# SCH_Satlla_4_Power_Board_2023-01-29.net
KiCad netlist of a schematic drawn in EasyEDA
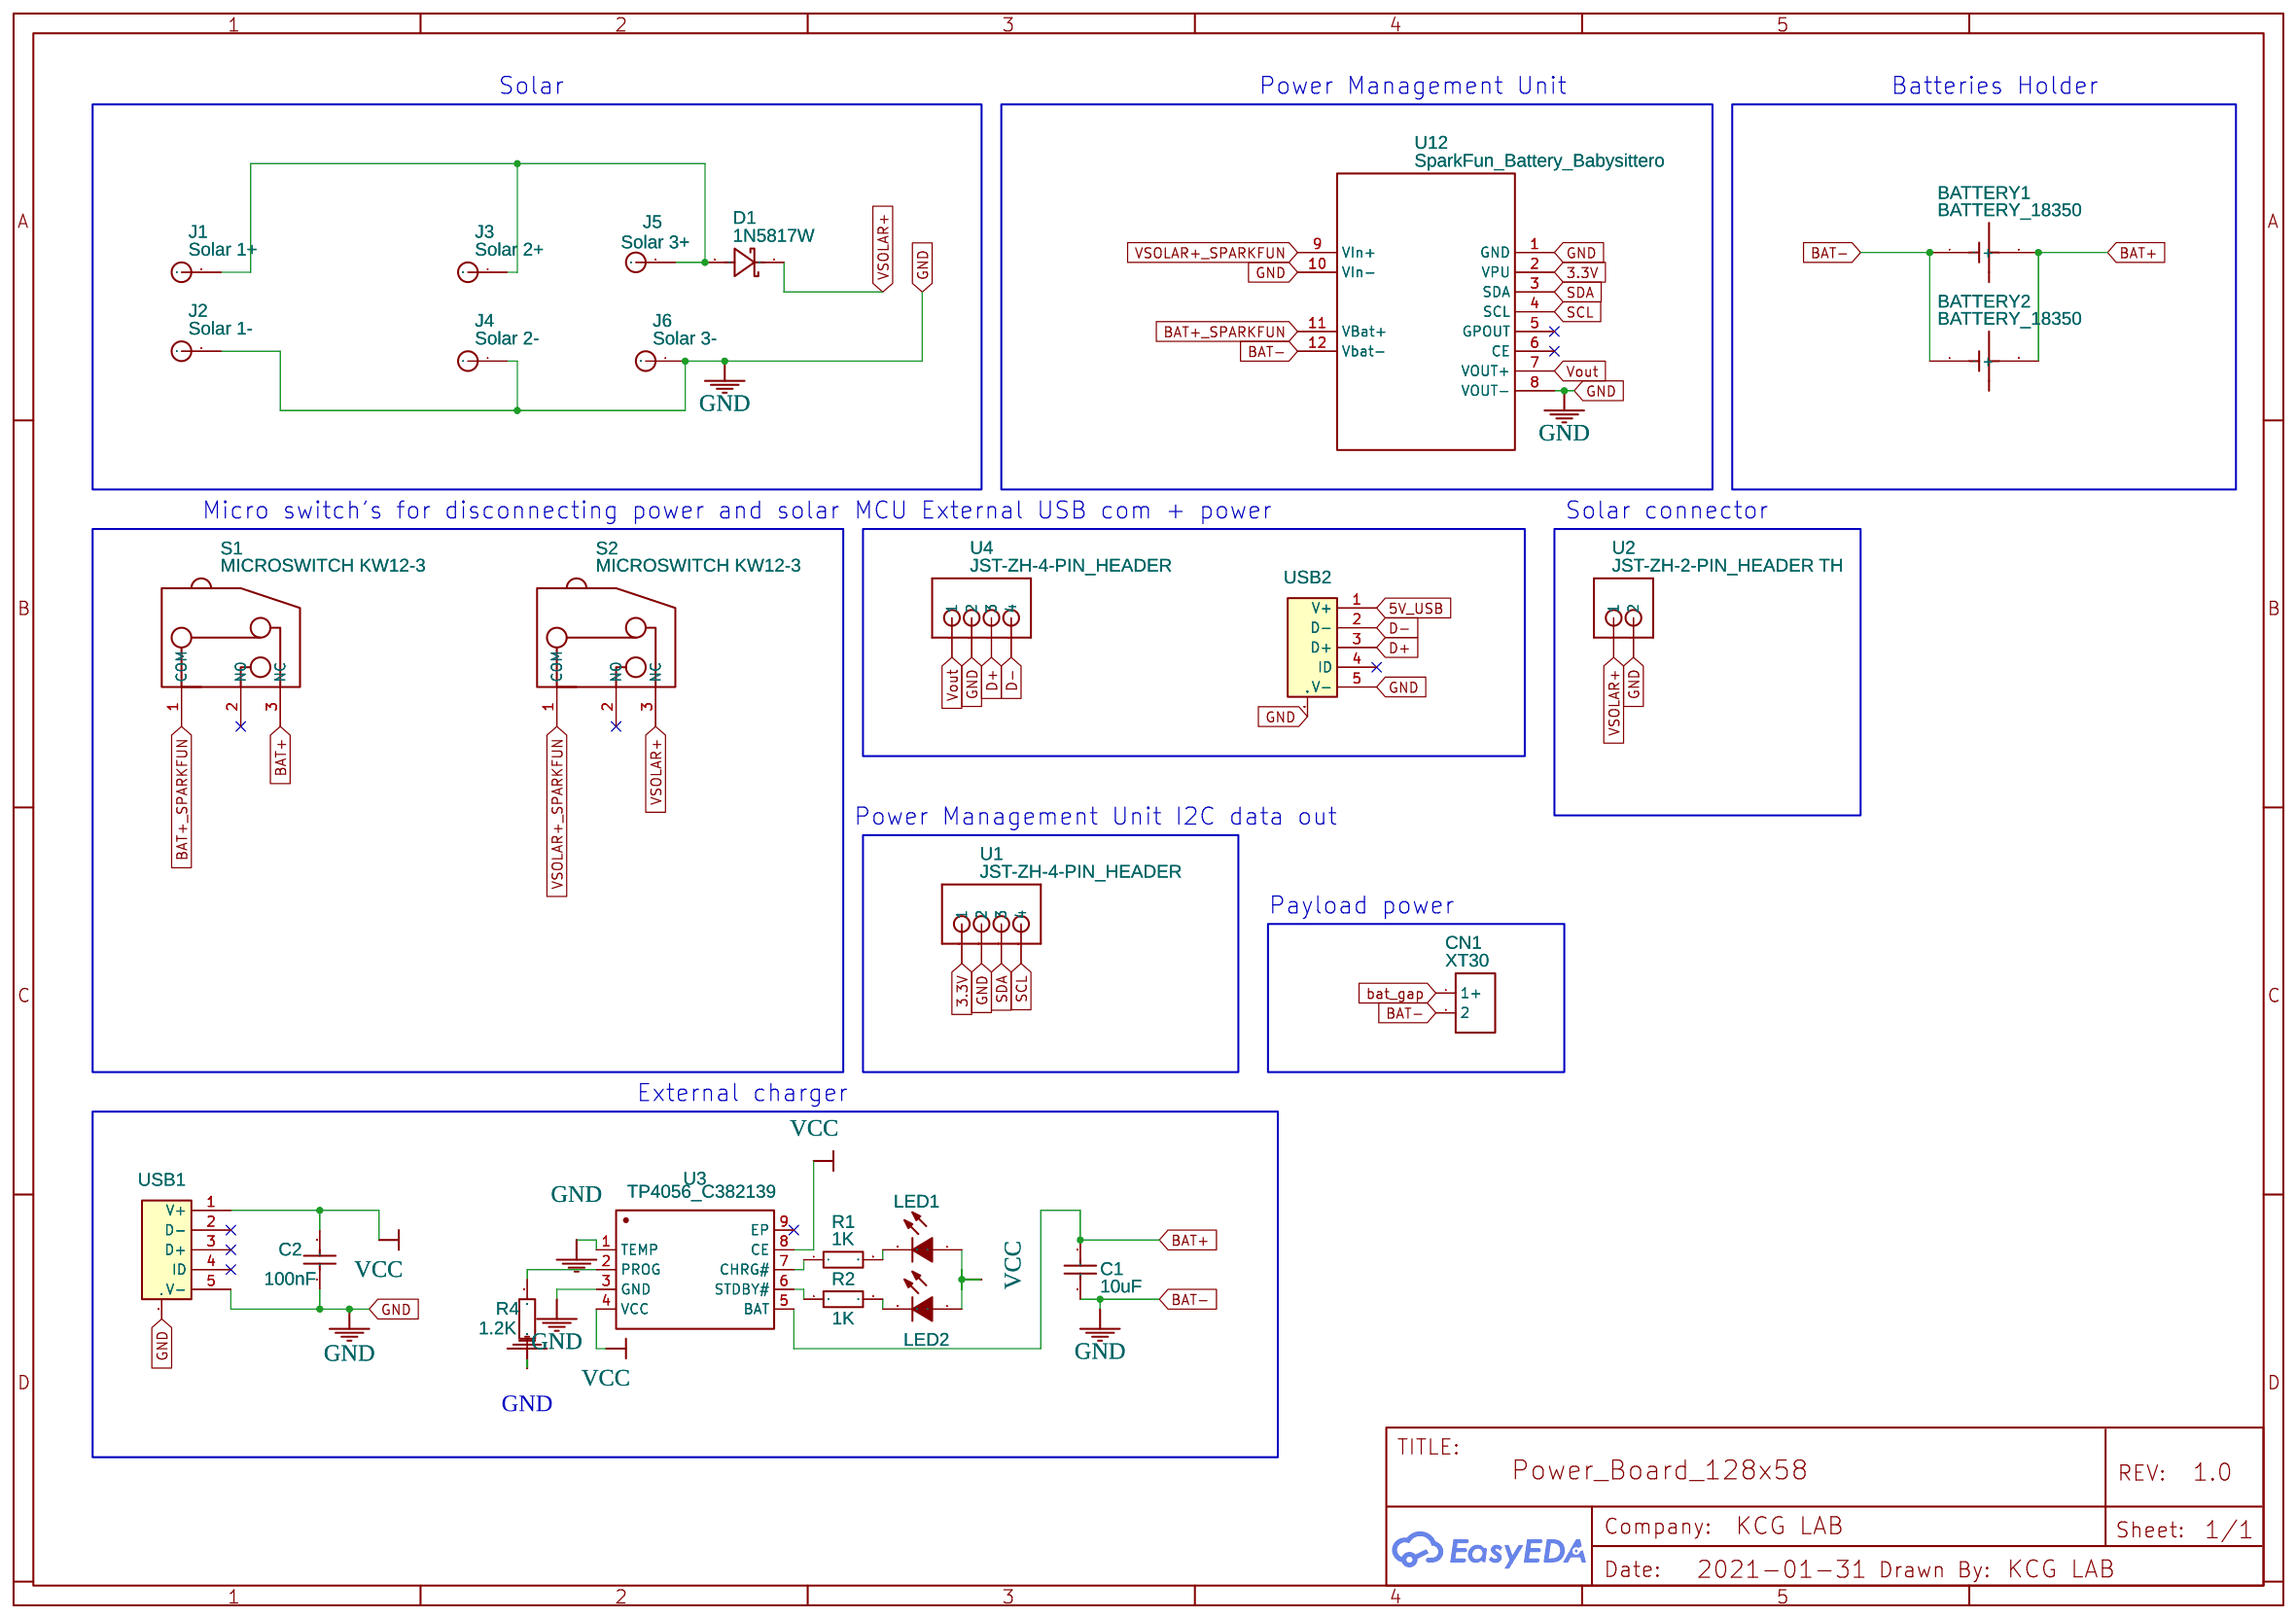
[diagram p0: schematic sheet]

(export (version "E")
  (design (tool "Eeschema 10.0.6"))
  (components
    (comp (ref "BATTERY1")
      (value "BATTERY_18350")
      (fields (field (name "BOM_Manufacturer Part") "file:///Users/leo/Downloads/54.PDF"))
      (libsource (lib "") (part "BATTERY_18350"))
    )
    (comp (ref "BATTERY2")
      (value "BATTERY_18350")
      (fields (field (name "BOM_Manufacturer Part") "file:///Users/leo/Downloads/54.PDF"))
      (libsource (lib "") (part "BATTERY_18350"))
    )
    (comp (ref "C1")
      (value "10uF")
      (fields
        (field (name "BOM_Manufacturer Part") "CL31A106KBHNNNE")
        (field (name "BOM_Supplier Part") "C13585")
      )
      (libsource (lib "") (part "CL31A106KBHNNNE"))
    )
    (comp (ref "C2")
      (value "100nF")
      (fields
        (field (name "BOM_Manufacturer Part") "CL31B104KBCNNNC")
        (field (name "BOM_Supplier Part") "C24497")
      )
      (libsource (lib "") (part "CL31B104KBCNNNC"))
    )
    (comp (ref "CN1")
      (value "XT30")
      (fields (field (name "BOM_Manufacturer Part") "XT30UPB-F") (field (name "BOM_Supplier Part") "C108769"))
      (libsource (lib "") (part "XT30UPB-F ARUN"))
    )
    (comp (ref "D1")
      (value "1N5817W")
      (fields (field (name "BOM_Supplier Part") "C727113"))
      (libsource (lib "") (part "1N5817W"))
    )
    (comp (ref "J1")
      (value "Solar 1+")
      (fields
        (field (name "BOM_Manufacturer Part") "RF130-1013BBS0741")
        (field (name "BOM_Supplier Part") "320030026")
      )
      (libsource (lib "") (part "Connector"))
    )
    (comp (ref "J2")
      (value "Solar 1-")
      (fields
        (field (name "BOM_Manufacturer Part") "RF130-1013BBS0741")
        (field (name "BOM_Supplier Part") "320030026")
      )
      (libsource (lib "") (part "Connector"))
    )
    (comp (ref "J3")
      (value "Solar 2+")
      (fields
        (field (name "BOM_Manufacturer Part") "RF130-1013BBS0741")
        (field (name "BOM_Supplier Part") "320030026")
      )
      (libsource (lib "") (part "Connector"))
    )
    (comp (ref "J4")
      (value "Solar 2-")
      (fields
        (field (name "BOM_Manufacturer Part") "RF130-1013BBS0741")
        (field (name "BOM_Supplier Part") "320030026")
      )
      (libsource (lib "") (part "Connector"))
    )
    (comp (ref "J5")
      (value "Solar 3+")
      (fields
        (field (name "BOM_Manufacturer Part") "RF130-1013BBS0741")
        (field (name "BOM_Supplier Part") "320030026")
      )
      (libsource (lib "") (part "Connector"))
    )
    (comp (ref "J6")
      (value "Solar 3-")
      (fields
        (field (name "BOM_Manufacturer Part") "RF130-1013BBS0741")
        (field (name "BOM_Supplier Part") "320030026")
      )
      (libsource (lib "") (part "Connector"))
    )
    (comp (ref "LED1")
      (value "17-21SURC/S530-A3/TR8")
      (fields (field (name "BOM_Supplier Part") "C72037"))
      (libsource (lib "") (part "Unknown_460_-190"))
    )
    (comp (ref "LED2")
      (value "17-21SURC/S530-A3/TR8")
      (fields (field (name "BOM_Supplier Part") "C72037"))
      (libsource (lib "") (part "Unknown_460_-160"))
    )
    (comp (ref "R1")
      (value "1K")
      (fields
        (field (name "BOM_Manufacturer Part") "RK73B2BTTD102J")
        (field (name "BOM_Supplier Part") "C192527")
      )
      (libsource (lib "") (part "RK73B2BTTD102J"))
    )
    (comp (ref "R2")
      (value "1K")
      (fields
        (field (name "BOM_Manufacturer Part") "RK73B2BTTD102J")
        (field (name "BOM_Supplier Part") "C192527")
      )
      (libsource (lib "") (part "RK73B2BTTD102J"))
    )
    (comp (ref "R4")
      (value "1.2K")
      (fields
        (field (name "BOM_Manufacturer Part") "RMC12061.2K1%N")
        (field (name "BOM_Supplier Part") "C269579")
      )
      (libsource (lib "") (part "RMC12061.2K1%N"))
    )
    (comp (ref "S1")
      (value "MICROSWITCH KW12-3")
      (fields (field (name "BOM_Manufacturer Part") "AVT34243") (field (name "BOM_Supplier Part") "173-8372"))
      (libsource (lib "") (part "MICROSWITCH KW12-3"))
    )
    (comp (ref "S2")
      (value "MICROSWITCH KW12-3")
      (fields (field (name "BOM_Manufacturer Part") "AVT34243") (field (name "BOM_Supplier Part") "173-8372"))
      (libsource (lib "") (part "MICROSWITCH KW12-3"))
    )
    (comp (ref "U1") (value "JST-ZH-4-PIN_HEADER") (libsource (lib "") (part "JST-ZH-4-PIN_HEADER")))
    (comp (ref "U2") (value "JST-ZH-2-PIN_HEADER TH") (libsource (lib "") (part "JST-ZH-2-PIN_HEADER TH")))
    (comp (ref "U3")
      (value "TP4056_C382139")
      (fields (field (name "BOM_Manufacturer Part") "TP4056") (field (name "BOM_Supplier Part") "C382139"))
      (libsource (lib "") (part "Unknown_345_-170"))
    )
    (comp (ref "U4") (value "JST-ZH-4-PIN_HEADER") (libsource (lib "") (part "JST-ZH-4-PIN_HEADER")))
    (comp (ref "U12")
      (value "SparkFun_Battery_Babysittero")
      (fields (field (name "BOM_Manufacturer Part") "SparkFun"))
      (libsource (lib "") (part "SparkFun_Battery_Babysittero"))
    )
    (comp (ref "USB1")
      (value "micro 5PFour-legged board7.2There is a column card point0.4m")
      (fields (field (name "BOM_Supplier Part") "C40943"))
      (libsource (lib "") (part "micro 5PFour-legged board7.2There is a column card point0.4m"))
    )
    (comp (ref "USB2")
      (value "micro 5PFour-legged board7.2There is a column card point0.4m")
      (fields (field (name "BOM_Supplier Part") "C40943"))
      (libsource (lib "") (part "micro 5PFour-legged board7.2There is a column card point0.4m"))
    )
  )
  (nets
    (net (code "1") (name "3.3V") (class "Default")
      (node (ref "U1") (pin "P1") (pinfunction "1_P1") (pintype "unspecified"))
      (node (ref "U12") (pin "2") (pinfunction "VPU_2") (pintype "unspecified"))
    )
    (net (code "2") (name "5V_USB") (class "Default")
      (node (ref "USB2") (pin "1") (pinfunction "V+_1") (pintype "unspecified"))
    )
    (net (code "3") (name "BAT+") (class "Default")
      (node (ref "BATTERY1") (pin "2") (pinfunction "+_2") (pintype "unspecified"))
      (node (ref "BATTERY2") (pin "2") (pinfunction "+_2") (pintype "unspecified"))
      (node (ref "C1") (pin "2") (pinfunction "2_2") (pintype "input"))
      (node (ref "S1") (pin "3") (pinfunction "NC_3") (pintype "unspecified"))
      (node (ref "U3") (pin "5") (pinfunction "BAT_5") (pintype "unspecified"))
    )
    (net (code "4") (name "BAT+_SPARKFUN") (class "Default")
      (node (ref "S1") (pin "1") (pinfunction "COM_1") (pintype "unspecified"))
      (node (ref "U12") (pin "11") (pinfunction "VBat+_11") (pintype "unspecified"))
    )
    (net (code "5") (name "BAT-") (class "Default")
      (node (ref "BATTERY1") (pin "1") (pinfunction "-_1") (pintype "unspecified"))
      (node (ref "BATTERY2") (pin "1") (pinfunction "-_1") (pintype "unspecified"))
      (node (ref "C1") (pin "1") (pinfunction "1_1") (pintype "input"))
      (node (ref "C2") (pin "1") (pinfunction "1_1") (pintype "input"))
      (node (ref "CN1") (pin "2") (pinfunction "2_2") (pintype "unspecified"))
      (node (ref "J2") (pin "1") (pinfunction "1_1") (pintype "unspecified"))
      (node (ref "J4") (pin "1") (pinfunction "1_1") (pintype "unspecified"))
      (node (ref "J6") (pin "1") (pinfunction "1_1") (pintype "unspecified"))
      (node (ref "R4") (pin "2") (pinfunction "2_2") (pintype "unspecified"))
      (node (ref "U1") (pin "P2") (pinfunction "2_P2") (pintype "unspecified"))
      (node (ref "U12") (pin "1") (pinfunction "GND_1") (pintype "unspecified"))
      (node (ref "U12") (pin "10") (pinfunction "VIn-_10") (pintype "unspecified"))
      (node (ref "U12") (pin "12") (pinfunction "Vbat-_12") (pintype "unspecified"))
      (node (ref "U12") (pin "8") (pinfunction "VOUT-_8") (pintype "unspecified"))
      (node (ref "U2") (pin "2") (pinfunction "2_2") (pintype "unspecified"))
      (node (ref "U3") (pin "1") (pinfunction "TEMP_1") (pintype "unspecified"))
      (node (ref "U3") (pin "3") (pinfunction "GND_3") (pintype "unspecified"))
      (node (ref "U4") (pin "P2") (pinfunction "2_P2") (pintype "unspecified"))
      (node (ref "USB1") (pin "0") (pinfunction "MTN6_0") (pintype "input"))
      (node (ref "USB1") (pin "5") (pinfunction "V-_5") (pintype "unspecified"))
      (node (ref "USB2") (pin "0") (pinfunction "MTN6_0") (pintype "input"))
      (node (ref "USB2") (pin "5") (pinfunction "V-_5") (pintype "unspecified"))
    )
    (net (code "6") (name "D+") (class "Default")
      (node (ref "U4") (pin "P3") (pinfunction "3_P3") (pintype "unspecified"))
      (node (ref "USB2") (pin "3") (pinfunction "D+_3") (pintype "unspecified"))
    )
    (net (code "7") (name "D-") (class "Default")
      (node (ref "U4") (pin "P4") (pinfunction "4_P4") (pintype "unspecified"))
      (node (ref "USB2") (pin "2") (pinfunction "D-_2") (pintype "unspecified"))
    )
    (net (code "8") (name "Net-(D1-A)") (class "Default")
      (node (ref "D1") (pin "2") (pinfunction "A_2") (pintype "unspecified"))
      (node (ref "J1") (pin "1") (pinfunction "1_1") (pintype "unspecified"))
      (node (ref "J3") (pin "1") (pinfunction "1_1") (pintype "unspecified"))
      (node (ref "J5") (pin "1") (pinfunction "1_1") (pintype "unspecified"))
    )
    (net (code "9") (name "Net-(LED1-C)") (class "Default")
      (node (ref "LED1") (pin "2") (pinfunction "C_2") (pintype "input"))
      (node (ref "R1") (pin "2") (pinfunction "2_2") (pintype "unspecified"))
    )
    (net (code "10") (name "Net-(LED2-C)") (class "Default")
      (node (ref "LED2") (pin "2") (pinfunction "C_2") (pintype "input"))
      (node (ref "R2") (pin "2") (pinfunction "2_2") (pintype "unspecified"))
    )
    (net (code "11") (name "Net-(U3-CHRG#)") (class "Default")
      (node (ref "R1") (pin "1") (pinfunction "1_1") (pintype "unspecified"))
      (node (ref "U3") (pin "7") (pinfunction "CHRG#_7") (pintype "unspecified"))
    )
    (net (code "12") (name "Net-(U3-PROG)") (class "Default")
      (node (ref "R4") (pin "1") (pinfunction "1_1") (pintype "unspecified"))
      (node (ref "U3") (pin "2") (pinfunction "PROG_2") (pintype "unspecified"))
    )
    (net (code "13") (name "Net-(U3-STDBY#)") (class "Default")
      (node (ref "R2") (pin "1") (pinfunction "1_1") (pintype "unspecified"))
      (node (ref "U3") (pin "6") (pinfunction "STDBY#_6") (pintype "unspecified"))
    )
    (net (code "14") (name "SCL") (class "Default")
      (node (ref "U1") (pin "P4") (pinfunction "4_P4") (pintype "unspecified"))
      (node (ref "U12") (pin "4") (pinfunction "SCL_4") (pintype "unspecified"))
    )
    (net (code "15") (name "SDA") (class "Default")
      (node (ref "U1") (pin "P3") (pinfunction "3_P3") (pintype "unspecified"))
      (node (ref "U12") (pin "3") (pinfunction "SDA_3") (pintype "unspecified"))
    )
    (net (code "16") (name "VCC") (class "Default")
      (node (ref "C2") (pin "2") (pinfunction "2_2") (pintype "input"))
      (node (ref "LED1") (pin "1") (pinfunction "A_1") (pintype "input"))
      (node (ref "LED2") (pin "1") (pinfunction "A_1") (pintype "input"))
      (node (ref "U3") (pin "4") (pinfunction "VCC_4") (pintype "unspecified"))
      (node (ref "U3") (pin "8") (pinfunction "CE_8") (pintype "unspecified"))
      (node (ref "USB1") (pin "1") (pinfunction "V+_1") (pintype "unspecified"))
    )
    (net (code "17") (name "VSOLAR+") (class "Default")
      (node (ref "D1") (pin "1") (pinfunction "C_1") (pintype "unspecified"))
      (node (ref "S2") (pin "3") (pinfunction "NC_3") (pintype "unspecified"))
      (node (ref "U2") (pin "1") (pinfunction "1_1") (pintype "unspecified"))
    )
    (net (code "18") (name "VSOLAR+_SPARKFUN") (class "Default")
      (node (ref "S2") (pin "1") (pinfunction "COM_1") (pintype "unspecified"))
      (node (ref "U12") (pin "9") (pinfunction "VIn+_9") (pintype "unspecified"))
    )
    (net (code "19") (name "Vout") (class "Default")
      (node (ref "U12") (pin "7") (pinfunction "VOUT+_7") (pintype "unspecified"))
      (node (ref "U4") (pin "P1") (pinfunction "1_P1") (pintype "unspecified"))
    )
    (net (code "20") (name "bat_gap") (class "Default")
      (node (ref "CN1") (pin "1") (pinfunction "1+_1") (pintype "unspecified"))
    )
    (net (code "21") (name "unconnected-(S1-NO-Pad2)") (class "Default")
      (node (ref "S1") (pin "2") (pinfunction "NO_2") (pintype "unspecified+no_connect"))
    )
    (net (code "22") (name "unconnected-(S2-NO-Pad2)") (class "Default")
      (node (ref "S2") (pin "2") (pinfunction "NO_2") (pintype "unspecified+no_connect"))
    )
    (net (code "23") (name "unconnected-(U3-EP-Pad9)") (class "Default")
      (node (ref "U3") (pin "9") (pinfunction "EP_9") (pintype "unspecified+no_connect"))
    )
    (net (code "24") (name "unconnected-(U12-CE-Pad6)") (class "Default")
      (node (ref "U12") (pin "6") (pinfunction "CE_6") (pintype "unspecified+no_connect"))
    )
    (net (code "25") (name "unconnected-(U12-GPOUT-Pad5)") (class "Default")
      (node (ref "U12") (pin "5") (pinfunction "GPOUT_5") (pintype "unspecified+no_connect"))
    )
    (net (code "26") (name "unconnected-(USB1-D+-Pad3)") (class "Default")
      (node (ref "USB1") (pin "3") (pinfunction "D+_3") (pintype "unspecified+no_connect"))
    )
    (net (code "27") (name "unconnected-(USB1-D--Pad2)") (class "Default")
      (node (ref "USB1") (pin "2") (pinfunction "D-_2") (pintype "unspecified+no_connect"))
    )
    (net (code "28") (name "unconnected-(USB1-ID-Pad4)") (class "Default")
      (node (ref "USB1") (pin "4") (pinfunction "ID_4") (pintype "unspecified+no_connect"))
    )
    (net (code "29") (name "unconnected-(USB2-ID-Pad4)") (class "Default")
      (node (ref "USB2") (pin "4") (pinfunction "ID_4") (pintype "unspecified+no_connect"))
    )
  )
)
